# Gyroscope.net
KiCad netlist of a schematic drawn in Altium Designer
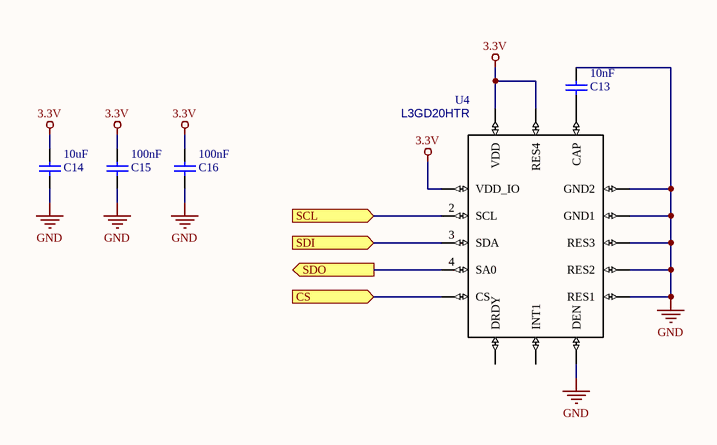
[diagram p0: Gyroscope.SchDoc]

(export (version "E")
  (design (tool "Eeschema 10.0.6"))
  (components
    (comp (ref "C13")
      (value "10nF")
      (footprint "0805 Footprint")
      (fields (field (name "Comment") "Cap"))
      (libsource (lib "RC0805FR-0751K1L") (part "Cap"))
    )
    (comp (ref "C14")
      (value "10uF")
      (footprint "0805 Footprint")
      (description "Near VDD")
      (fields (field (name "Comment") "Cap"))
      (libsource (lib "RC0805FR-0751K1L") (part "Cap"))
    )
    (comp (ref "C15")
      (value "100nF")
      (footprint "0603 to 0805 SMD")
      (description "Near VDD")
      (fields (field (name "Comment") "Cap"))
      (libsource (lib "RC0805FR-0751K1L") (part "Cap"))
    )
    (comp (ref "C16")
      (value "100nF")
      (footprint "0603 to 0805 SMD")
      (description "Near VDD_IO")
      (fields (field (name "Comment") "Cap"))
      (libsource (lib "RC0805FR-0751K1L") (part "Cap"))
    )
    (comp (ref "U4")
      (value "L3GD20H")
      (footprint "L3GD20HTR")
      (description "Gyroscope L3GD20H Series 3.6 V 6.1 mA Three-Axis Digital Output Gyroscope - LGA-16")
      (fields (field (name "MF") "STMicroelectronics") (field (name "MP") "L3GD20HTR"))
      (libsource (lib "AvionicsParts") (part "L3GD20H"))
    )
  )
  (nets
    (net (code "1") (name "/CS") (class "Default")
      (node (ref "U4") (pin "5") (pinfunction "CS_5") (pintype "bidirectional"))
    )
    (net (code "2") (name "/SCL") (class "Default")
      (node (ref "U4") (pin "2") (pinfunction "SCL_2") (pintype "bidirectional"))
    )
    (net (code "3") (name "/SDI") (class "Default")
      (node (ref "U4") (pin "3") (pinfunction "SDA_3") (pintype "bidirectional"))
    )
    (net (code "4") (name "/SDO") (class "Default")
      (node (ref "U4") (pin "4") (pinfunction "SA0_4") (pintype "bidirectional"))
    )
    (net (code "5") (name "3.3V") (class "Default")
      (node (ref "C14") (pin "2") (pinfunction "2_2") (pintype "passive"))
      (node (ref "C15") (pin "2") (pinfunction "2_2") (pintype "passive"))
      (node (ref "C16") (pin "2") (pinfunction "2_2") (pintype "passive"))
      (node (ref "U4") (pin "1") (pinfunction "VDD_IO_1") (pintype "bidirectional"))
      (node (ref "U4") (pin "15") (pinfunction "RES4_15") (pintype "bidirectional"))
      (node (ref "U4") (pin "16") (pinfunction "VDD_16") (pintype "bidirectional"))
    )
    (net (code "6") (name "GND") (class "Default")
      (node (ref "C13") (pin "2") (pinfunction "2_2") (pintype "passive"))
      (node (ref "C14") (pin "1") (pinfunction "1_1") (pintype "passive"))
      (node (ref "C15") (pin "1") (pinfunction "1_1") (pintype "passive"))
      (node (ref "C16") (pin "1") (pinfunction "1_1") (pintype "passive"))
      (node (ref "U4") (pin "10") (pinfunction "RES2_10") (pintype "bidirectional"))
      (node (ref "U4") (pin "11") (pinfunction "RES3_11") (pintype "bidirectional"))
      (node (ref "U4") (pin "12") (pinfunction "GND1_12") (pintype "bidirectional"))
      (node (ref "U4") (pin "13") (pinfunction "GND2_13") (pintype "bidirectional"))
      (node (ref "U4") (pin "8") (pinfunction "DEN_8") (pintype "bidirectional"))
      (node (ref "U4") (pin "9") (pinfunction "RES1_9") (pintype "bidirectional"))
    )
    (net (code "7") (name "Net-(U4-CAP)") (class "Default")
      (node (ref "C13") (pin "1") (pinfunction "1_1") (pintype "passive"))
      (node (ref "U4") (pin "14") (pinfunction "CAP_14") (pintype "bidirectional"))
    )
    (net (code "8") (name "unconnected-(U4-DRDY-Pad6)") (class "Default")
      (node (ref "U4") (pin "6") (pinfunction "DRDY_6") (pintype "bidirectional"))
    )
    (net (code "9") (name "unconnected-(U4-INT1-Pad7)") (class "Default")
      (node (ref "U4") (pin "7") (pinfunction "INT1_7") (pintype "bidirectional"))
    )
  )
)
